# attiny_rc_switch_th_schematic.net
KiCad netlist of a schematic drawn in EAGLE
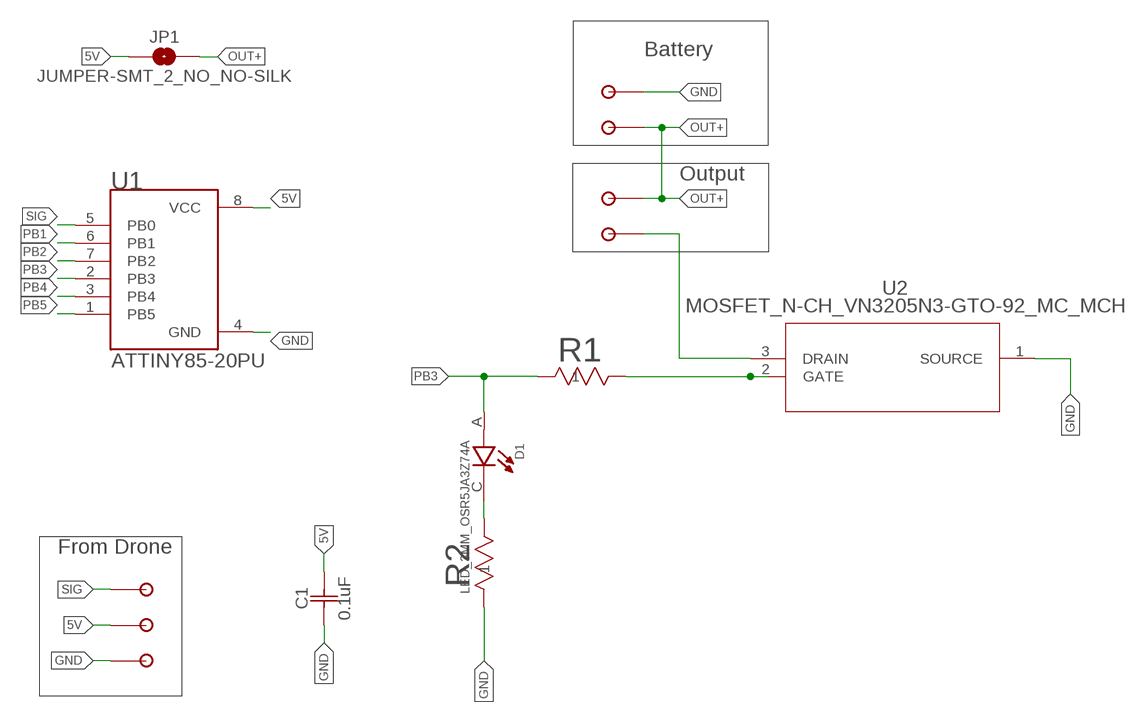
[diagram p0: schematic, sheet 1]

(export (version "E")
  (design (tool "Eeschema 10.0.6"))
  (components
    (comp (ref "C1")
      (value "0.1uF")
      (footprint "eagle-import:K10XK10X7RF5UH5")
      (fields
        (field (name "MANUFACTURER_PART_NUMBER") "K103K10X7RF5UH5")
        (field (name "COPYRIGHT") "Copyright (C) 2024 Ultra Librarian. All rights reserved.")
      )
      (libsource (lib "eagle-import") (part "CAPACITOR_CERAMIC_50V_K10XK10X7RF5UH5K103K10X7RF5UH5_VIS"))
    )
    (comp (ref "D1")
      (value "LED_3MM_OSR5JA3Z74A")
      (footprint "eagle-import:OSR5JA3Z74A")
      (fields (field (name "MF") "optosupply") (field (name "MP") "OSR5JA3Z74A"))
      (libsource (lib "eagle-import") (part "LED_3MM_OSR5JA3Z74A"))
    )
    (comp (ref "JP1")
      (value "JUMPER-SMT_2_NO_NO-SILK")
      (footprint "eagle-import:SMT-JUMPER_2_NO_NO-SILK")
      (libsource (lib "eagle-import") (part "JUMPER-SMT_2_NO_NO-SILK"))
    )
    (comp (ref "R1")
      (value "RESISTOR_1/8W_CF18JTSTA_CF18_STP")
      (footprint "eagle-import:RESISTOR_1_8W_CF18JT")
      (fields
        (field (name "MANUFACTURER_PART_NUMBER") "CF18JT100K")
        (field (name "COPYRIGHT") "Copyright (C) 2025 Ultra Librarian. All rights reserved.")
      )
      (libsource (lib "eagle-import") (part "RESISTOR_1/8W_CF18JTSTA_CF18_STP"))
    )
    (comp (ref "R2")
      (value "RESISTOR_1/8W_CF18JTSTA_CF18_STP")
      (footprint "eagle-import:RESISTOR_1_8W_CF18JT")
      (fields
        (field (name "MANUFACTURER_PART_NUMBER") "CF18JT100K")
        (field (name "COPYRIGHT") "Copyright (C) 2025 Ultra Librarian. All rights reserved.")
      )
      (libsource (lib "eagle-import") (part "RESISTOR_1/8W_CF18JTSTA_CF18_STP"))
    )
    (comp (ref "U$1")
      (value "SMD_PAD_NO_STENCIL")
      (footprint "eagle-import:SMD_PAD_NO_STENCIL")
      (libsource (lib "eagle-import") (part "SMD_PAD_NO_STENCIL"))
    )
    (comp (ref "U$2")
      (value "SMD_PAD_NO_STENCIL")
      (footprint "eagle-import:SMD_PAD_NO_STENCIL")
      (libsource (lib "eagle-import") (part "SMD_PAD_NO_STENCIL"))
    )
    (comp (ref "U$3")
      (value "SMD_PAD_NO_STENCIL")
      (footprint "eagle-import:SMD_PAD_NO_STENCIL")
      (libsource (lib "eagle-import") (part "SMD_PAD_NO_STENCIL"))
    )
    (comp (ref "U$4")
      (value "SMD_PAD_NO_STENCIL")
      (footprint "eagle-import:SMD_PAD_NO_STENCIL")
      (libsource (lib "eagle-import") (part "SMD_PAD_NO_STENCIL"))
    )
    (comp (ref "U$5")
      (value "SMD_PAD_NO_STENCIL")
      (footprint "eagle-import:SMD_PAD_NO_STENCIL")
      (libsource (lib "eagle-import") (part "SMD_PAD_NO_STENCIL"))
    )
    (comp (ref "U$6")
      (value "SMD_PAD_NO_STENCIL")
      (footprint "eagle-import:SMD_PAD_NO_STENCIL")
      (libsource (lib "eagle-import") (part "SMD_PAD_NO_STENCIL"))
    )
    (comp (ref "U$7")
      (value "SMD_PAD_NO_STENCIL")
      (footprint "eagle-import:SMD_PAD_NO_STENCIL")
      (libsource (lib "eagle-import") (part "SMD_PAD_NO_STENCIL"))
    )
    (comp (ref "U1")
      (value "ATTINY85-20PU")
      (footprint "eagle-import:ATTINY85-20PU")
      (fields (field (name "MANUFACTURER") "Atmel "))
      (libsource (lib "eagle-import") (part "ATTINY85-20PU"))
    )
    (comp (ref "U2")
      (value "MOSFET_N-CH_VN3205N3-GTO-92_MC_MCH")
      (footprint "eagle-import:MOSFET_N-CH_VN3205N3-G")
      (fields
        (field (name "MANUFACTURER_PART_NUMBER") "VN3205N3-G")
        (field (name "COPYRIGHT") "Copyright (C) 2025 Ultra Librarian. All rights reserved.")
      )
      (libsource (lib "eagle-import") (part "MOSFET_N-CH_VN3205N3-GTO-92_MC_MCH"))
    )
  )
  (nets
    (net (code "1") (name "5V") (class "Default")
      (node (ref "C1") (pin "2") (pinfunction "2_2") (pintype "passive"))
      (node (ref "JP1") (pin "1") (pinfunction "1_1") (pintype "passive"))
      (node (ref "U$1") (pin "P$1") (pinfunction "P$1_P$1") (pintype "bidirectional"))
      (node (ref "U1") (pin "8") (pinfunction "VCC_8") (pintype "power_in"))
    )
    (net (code "2") (name "GND") (class "Default")
      (node (ref "C1") (pin "1") (pinfunction "1_1") (pintype "passive"))
      (node (ref "R2") (pin "1") (pinfunction "1_1") (pintype "passive"))
      (node (ref "U$2") (pin "P$1") (pinfunction "P$1_P$1") (pintype "bidirectional"))
      (node (ref "U$6") (pin "P$1") (pinfunction "P$1_P$1") (pintype "bidirectional"))
      (node (ref "U1") (pin "4") (pinfunction "GND_4") (pintype "power_in"))
      (node (ref "U2") (pin "1") (pinfunction "SOURCE_1") (pintype "passive"))
    )
    (net (code "3") (name "Net-(D1-PadC)") (class "Default")
      (node (ref "D1") (pin "C") (pinfunction "C_C") (pintype "passive"))
      (node (ref "R2") (pin "2") (pinfunction "2_2") (pintype "passive"))
    )
    (net (code "4") (name "Net-(U2-DRAIN)") (class "Default")
      (node (ref "U$3") (pin "P$1") (pinfunction "P$1_P$1") (pintype "bidirectional"))
      (node (ref "U2") (pin "3") (pinfunction "DRAIN_3") (pintype "passive"))
    )
    (net (code "5") (name "Net-(U2-GATE)") (class "Default")
      (node (ref "R1") (pin "2") (pinfunction "2_2") (pintype "passive"))
      (node (ref "U2") (pin "2") (pinfunction "GATE_2") (pintype "passive"))
    )
    (net (code "6") (name "OUT+") (class "Default")
      (node (ref "JP1") (pin "2") (pinfunction "2_2") (pintype "passive"))
      (node (ref "U$4") (pin "P$1") (pinfunction "P$1_P$1") (pintype "bidirectional"))
      (node (ref "U$5") (pin "P$1") (pinfunction "P$1_P$1") (pintype "bidirectional"))
    )
    (net (code "7") (name "PB1") (class "Default")
      (node (ref "U1") (pin "6") (pinfunction "PB1_6") (pintype "bidirectional"))
    )
    (net (code "8") (name "PB2") (class "Default")
      (node (ref "U1") (pin "7") (pinfunction "PB2_7") (pintype "bidirectional"))
    )
    (net (code "9") (name "PB3") (class "Default")
      (node (ref "D1") (pin "A") (pinfunction "A_A") (pintype "passive"))
      (node (ref "R1") (pin "1") (pinfunction "1_1") (pintype "passive"))
      (node (ref "U1") (pin "2") (pinfunction "PB3_2") (pintype "bidirectional"))
    )
    (net (code "10") (name "PB4") (class "Default")
      (node (ref "U1") (pin "3") (pinfunction "PB4_3") (pintype "bidirectional"))
    )
    (net (code "11") (name "PB5") (class "Default")
      (node (ref "U1") (pin "1") (pinfunction "PB5_1") (pintype "bidirectional"))
    )
    (net (code "12") (name "SIG") (class "Default")
      (node (ref "U$7") (pin "P$1") (pinfunction "P$1_P$1") (pintype "bidirectional"))
      (node (ref "U1") (pin "5") (pinfunction "PB0_5") (pintype "bidirectional"))
    )
  )
)
